# SchematicEagle.net
KiCad netlist of a schematic drawn in EAGLE
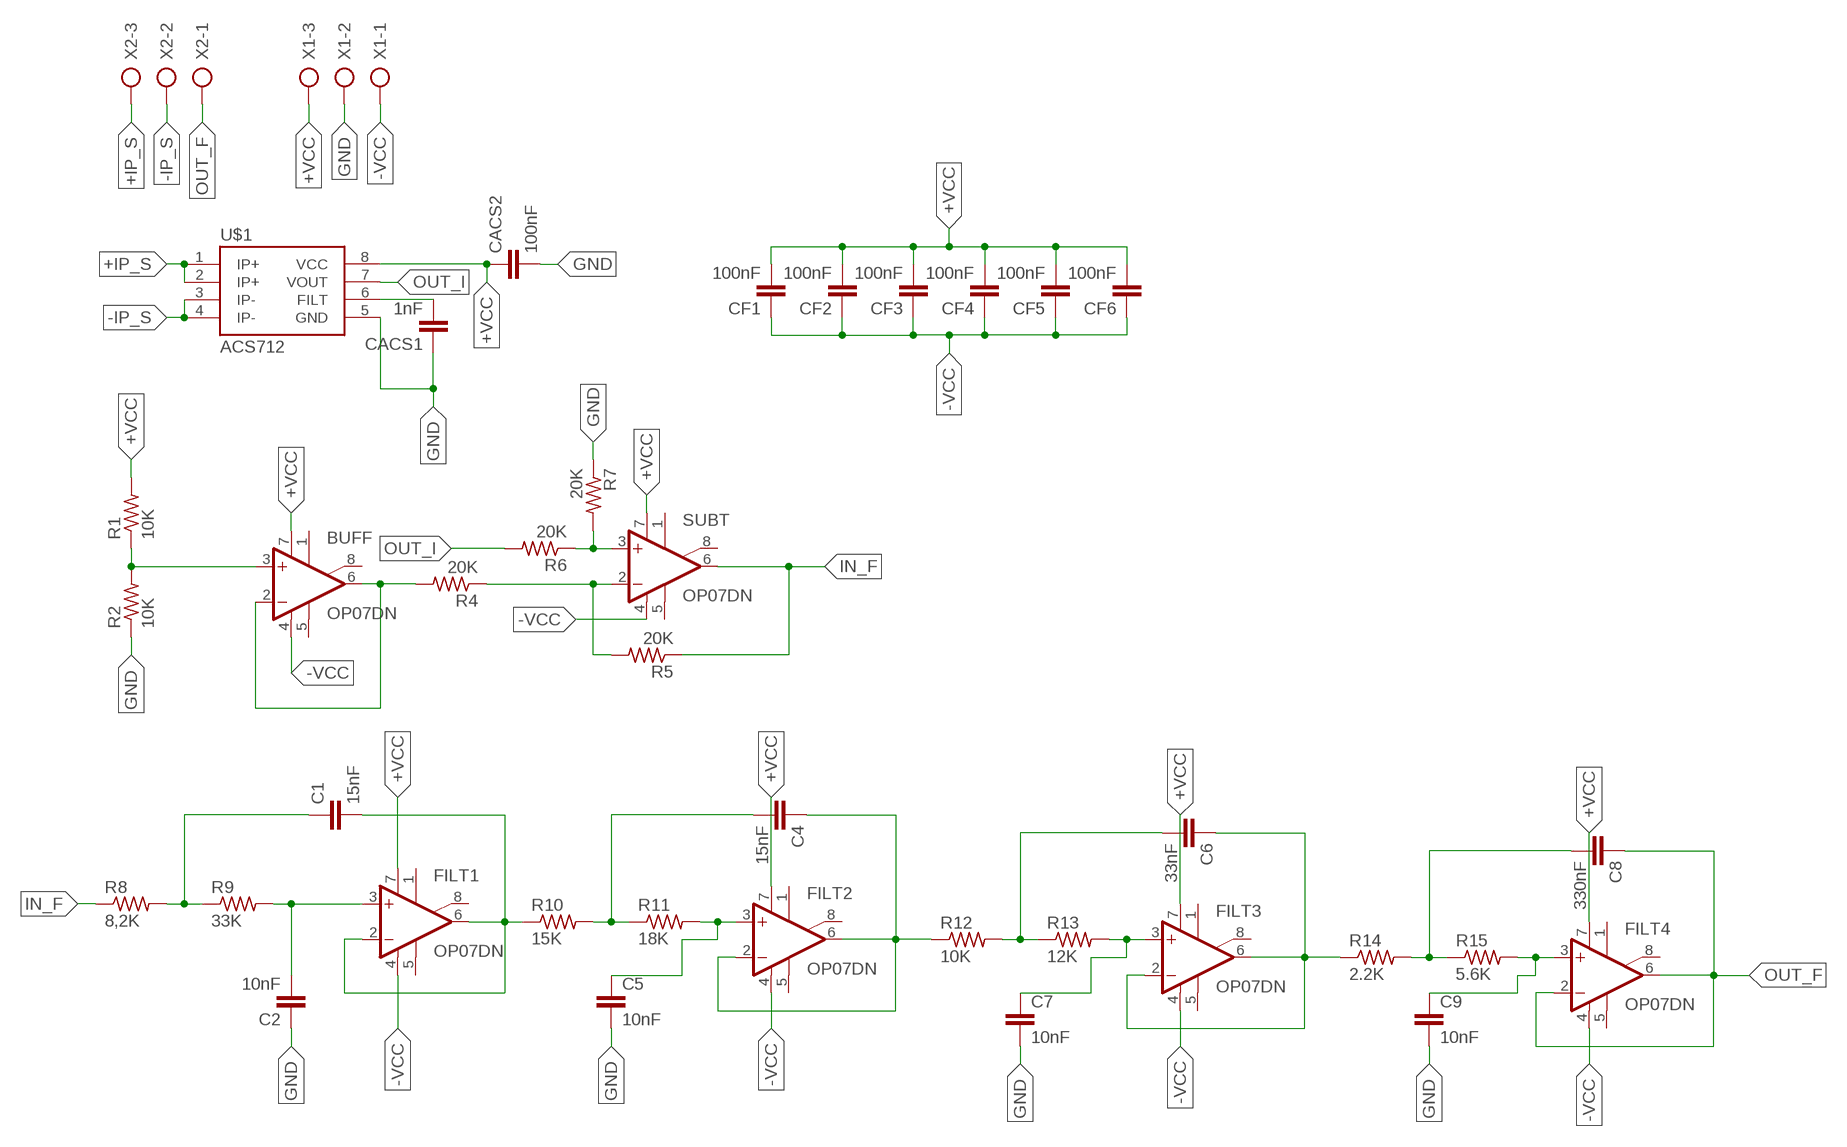
[diagram p0: schematic, sheet 1]

(export (version "E")
  (design (tool "Eeschema 10.0.6"))
  (components
    (comp (ref "BUFF")
      (value "OP07DN")
      (footprint "eagle-import:DIL08")
      (libsource (lib "eagle-import") (part "OP07ND"))
    )
    (comp (ref "C1")
      (value "15nF")
      (footprint "eagle-import:C050-024X044")
      (libsource (lib "eagle-import") (part "C-EU050-024X044"))
    )
    (comp (ref "C2")
      (value "10nF")
      (footprint "eagle-import:C050-024X044")
      (libsource (lib "eagle-import") (part "C-EU050-024X044"))
    )
    (comp (ref "C4")
      (value "15nF")
      (footprint "eagle-import:C050-024X044")
      (libsource (lib "eagle-import") (part "C-EU050-024X044"))
    )
    (comp (ref "C5")
      (value "10nF")
      (footprint "eagle-import:C050-024X044")
      (libsource (lib "eagle-import") (part "C-EU050-024X044"))
    )
    (comp (ref "C6")
      (value "33nF")
      (footprint "eagle-import:C050-024X044")
      (libsource (lib "eagle-import") (part "C-EU050-024X044"))
    )
    (comp (ref "C7")
      (value "10nF")
      (footprint "eagle-import:C050-024X044")
      (libsource (lib "eagle-import") (part "C-EU050-024X044"))
    )
    (comp (ref "C8")
      (value "330nF")
      (footprint "eagle-import:C050-024X044")
      (libsource (lib "eagle-import") (part "C-EU050-024X044"))
    )
    (comp (ref "C9")
      (value "10nF")
      (footprint "eagle-import:C050-024X044")
      (libsource (lib "eagle-import") (part "C-EU050-024X044"))
    )
    (comp (ref "CACS1")
      (value "1nF")
      (footprint "eagle-import:C050-024X044")
      (libsource (lib "eagle-import") (part "C-EU050-024X044"))
    )
    (comp (ref "CACS2")
      (value "100nF")
      (footprint "eagle-import:C050-024X044")
      (libsource (lib "eagle-import") (part "C-EU050-024X044"))
    )
    (comp (ref "CF1")
      (value "100nF")
      (footprint "eagle-import:C050-024X044")
      (libsource (lib "eagle-import") (part "C-EU050-024X044"))
    )
    (comp (ref "CF2")
      (value "100nF")
      (footprint "eagle-import:C050-024X044")
      (libsource (lib "eagle-import") (part "C-EU050-024X044"))
    )
    (comp (ref "CF3")
      (value "100nF")
      (footprint "eagle-import:C050-024X044")
      (libsource (lib "eagle-import") (part "C-EU050-024X044"))
    )
    (comp (ref "CF4")
      (value "100nF")
      (footprint "eagle-import:C050-024X044")
      (libsource (lib "eagle-import") (part "C-EU050-024X044"))
    )
    (comp (ref "CF5")
      (value "100nF")
      (footprint "eagle-import:C050-024X044")
      (libsource (lib "eagle-import") (part "C-EU050-024X044"))
    )
    (comp (ref "CF6")
      (value "100nF")
      (footprint "eagle-import:C050-024X044")
      (libsource (lib "eagle-import") (part "C-EU050-024X044"))
    )
    (comp (ref "FILT1")
      (value "OP07DN")
      (footprint "eagle-import:DIL08")
      (libsource (lib "eagle-import") (part "OP07ND"))
    )
    (comp (ref "FILT2")
      (value "OP07DN")
      (footprint "eagle-import:DIL08")
      (libsource (lib "eagle-import") (part "OP07ND"))
    )
    (comp (ref "FILT3")
      (value "OP07DN")
      (footprint "eagle-import:DIL08")
      (libsource (lib "eagle-import") (part "OP07ND"))
    )
    (comp (ref "FILT4")
      (value "OP07DN")
      (footprint "eagle-import:DIL08")
      (libsource (lib "eagle-import") (part "OP07ND"))
    )
    (comp (ref "R1")
      (value "10K")
      (footprint "eagle-import:0207_7")
      (libsource (lib "eagle-import") (part "R-US_0207/7"))
    )
    (comp (ref "R2")
      (value "10K")
      (footprint "eagle-import:0207_7")
      (libsource (lib "eagle-import") (part "R-US_0207/7"))
    )
    (comp (ref "R4")
      (value "20K")
      (footprint "eagle-import:0207_7")
      (libsource (lib "eagle-import") (part "R-US_0207/7"))
    )
    (comp (ref "R5")
      (value "20K")
      (footprint "eagle-import:0207_7")
      (libsource (lib "eagle-import") (part "R-US_0207/7"))
    )
    (comp (ref "R6")
      (value "20K")
      (footprint "eagle-import:0207_7")
      (libsource (lib "eagle-import") (part "R-US_0207/7"))
    )
    (comp (ref "R7")
      (value "20K")
      (footprint "eagle-import:0207_7")
      (libsource (lib "eagle-import") (part "R-US_0207/7"))
    )
    (comp (ref "R8")
      (value "8,2K")
      (footprint "eagle-import:0207_7")
      (libsource (lib "eagle-import") (part "R-US_0207/7"))
    )
    (comp (ref "R9")
      (value "33K")
      (footprint "eagle-import:0207_7")
      (libsource (lib "eagle-import") (part "R-US_0207/7"))
    )
    (comp (ref "R10")
      (value "15K")
      (footprint "eagle-import:0207_7")
      (libsource (lib "eagle-import") (part "R-US_0207/7"))
    )
    (comp (ref "R11")
      (value "18K")
      (footprint "eagle-import:0207_7")
      (libsource (lib "eagle-import") (part "R-US_0207/7"))
    )
    (comp (ref "R12")
      (value "10K")
      (footprint "eagle-import:0207_7")
      (libsource (lib "eagle-import") (part "R-US_0207/7"))
    )
    (comp (ref "R13")
      (value "12K")
      (footprint "eagle-import:0207_7")
      (libsource (lib "eagle-import") (part "R-US_0207/7"))
    )
    (comp (ref "R14")
      (value "2.2K")
      (footprint "eagle-import:0207_7")
      (libsource (lib "eagle-import") (part "R-US_0207/7"))
    )
    (comp (ref "R15")
      (value "5.6K")
      (footprint "eagle-import:0207_7")
      (libsource (lib "eagle-import") (part "R-US_0207/7"))
    )
    (comp (ref "SUBT")
      (value "OP07DN")
      (footprint "eagle-import:DIL08")
      (libsource (lib "eagle-import") (part "OP07ND"))
    )
    (comp (ref "U$1")
      (value "ACS712")
      (footprint "eagle-import:SO08")
      (libsource (lib "eagle-import") (part "ACS712"))
    )
    (comp (ref "X1")
      (value "AK500/3")
      (footprint "eagle-import:AK500_3")
      (libsource (lib "eagle-import") (part "AK500/3"))
    )
    (comp (ref "X2")
      (value "AK500/3")
      (footprint "eagle-import:AK500_3")
      (libsource (lib "eagle-import") (part "AK500/3"))
    )
  )
  (nets
    (net (code "1") (name "+IP_S") (class "Default")
      (node (ref "U$1") (pin "1") (pinfunction "IP+_1") (pintype "bidirectional"))
      (node (ref "U$1") (pin "2") (pinfunction "IP+_2") (pintype "bidirectional"))
      (node (ref "X2") (pin "3") (pinfunction "KL_3") (pintype "passive"))
    )
    (net (code "2") (name "+VCC") (class "Default")
      (node (ref "BUFF") (pin "7") (pinfunction "V+_7") (pintype "power_in"))
      (node (ref "CACS2") (pin "1") (pinfunction "1_1") (pintype "passive"))
      (node (ref "CF1") (pin "2") (pinfunction "2_2") (pintype "passive"))
      (node (ref "CF2") (pin "2") (pinfunction "2_2") (pintype "passive"))
      (node (ref "CF3") (pin "2") (pinfunction "2_2") (pintype "passive"))
      (node (ref "CF4") (pin "2") (pinfunction "2_2") (pintype "passive"))
      (node (ref "CF5") (pin "2") (pinfunction "2_2") (pintype "passive"))
      (node (ref "CF6") (pin "2") (pinfunction "2_2") (pintype "passive"))
      (node (ref "FILT1") (pin "7") (pinfunction "V+_7") (pintype "power_in"))
      (node (ref "FILT2") (pin "7") (pinfunction "V+_7") (pintype "power_in"))
      (node (ref "FILT3") (pin "7") (pinfunction "V+_7") (pintype "power_in"))
      (node (ref "FILT4") (pin "7") (pinfunction "V+_7") (pintype "power_in"))
      (node (ref "R1") (pin "2") (pinfunction "2_2") (pintype "passive"))
      (node (ref "SUBT") (pin "7") (pinfunction "V+_7") (pintype "power_in"))
      (node (ref "U$1") (pin "8") (pinfunction "VCC_8") (pintype "bidirectional"))
      (node (ref "X1") (pin "3") (pinfunction "KL_3") (pintype "passive"))
    )
    (net (code "3") (name "-IP_S") (class "Default")
      (node (ref "U$1") (pin "3") (pinfunction "IP-_3") (pintype "bidirectional"))
      (node (ref "U$1") (pin "4") (pinfunction "IP-_4") (pintype "bidirectional"))
      (node (ref "X2") (pin "2") (pinfunction "KL_2") (pintype "passive"))
    )
    (net (code "4") (name "-VCC") (class "Default")
      (node (ref "BUFF") (pin "4") (pinfunction "V-_4") (pintype "power_in"))
      (node (ref "CF1") (pin "1") (pinfunction "1_1") (pintype "passive"))
      (node (ref "CF2") (pin "1") (pinfunction "1_1") (pintype "passive"))
      (node (ref "CF3") (pin "1") (pinfunction "1_1") (pintype "passive"))
      (node (ref "CF4") (pin "1") (pinfunction "1_1") (pintype "passive"))
      (node (ref "CF5") (pin "1") (pinfunction "1_1") (pintype "passive"))
      (node (ref "CF6") (pin "1") (pinfunction "1_1") (pintype "passive"))
      (node (ref "FILT1") (pin "4") (pinfunction "V-_4") (pintype "power_in"))
      (node (ref "FILT2") (pin "4") (pinfunction "V-_4") (pintype "power_in"))
      (node (ref "FILT3") (pin "4") (pinfunction "V-_4") (pintype "power_in"))
      (node (ref "FILT4") (pin "4") (pinfunction "V-_4") (pintype "power_in"))
      (node (ref "SUBT") (pin "4") (pinfunction "V-_4") (pintype "power_in"))
      (node (ref "X1") (pin "1") (pinfunction "KL_1") (pintype "passive"))
    )
    (net (code "5") (name "GND") (class "Default")
      (node (ref "C2") (pin "1") (pinfunction "1_1") (pintype "passive"))
      (node (ref "C5") (pin "2") (pinfunction "2_2") (pintype "passive"))
      (node (ref "C7") (pin "2") (pinfunction "2_2") (pintype "passive"))
      (node (ref "C9") (pin "2") (pinfunction "2_2") (pintype "passive"))
      (node (ref "CACS1") (pin "1") (pinfunction "1_1") (pintype "passive"))
      (node (ref "CACS2") (pin "2") (pinfunction "2_2") (pintype "passive"))
      (node (ref "R2") (pin "1") (pinfunction "1_1") (pintype "passive"))
      (node (ref "R7") (pin "1") (pinfunction "1_1") (pintype "passive"))
      (node (ref "U$1") (pin "5") (pinfunction "GND_5") (pintype "bidirectional"))
      (node (ref "X1") (pin "2") (pinfunction "KL_2") (pintype "passive"))
    )
    (net (code "6") (name "IN_F") (class "Default")
      (node (ref "R5") (pin "1") (pinfunction "1_1") (pintype "passive"))
      (node (ref "R8") (pin "1") (pinfunction "1_1") (pintype "passive"))
      (node (ref "SUBT") (pin "6") (pinfunction "OUT_6") (pintype "output"))
    )
    (net (code "7") (name "Net-(BUFF-+IN)") (class "Default")
      (node (ref "BUFF") (pin "3") (pinfunction "+IN_3") (pintype "input"))
      (node (ref "R1") (pin "1") (pinfunction "1_1") (pintype "passive"))
      (node (ref "R2") (pin "2") (pinfunction "2_2") (pintype "passive"))
    )
    (net (code "8") (name "Net-(BUFF--IN)") (class "Default")
      (node (ref "BUFF") (pin "2") (pinfunction "-IN_2") (pintype "input"))
      (node (ref "BUFF") (pin "6") (pinfunction "OUT_6") (pintype "output"))
      (node (ref "R4") (pin "2") (pinfunction "2_2") (pintype "passive"))
    )
    (net (code "9") (name "Net-(C1-Pad1)") (class "Default")
      (node (ref "C1") (pin "1") (pinfunction "1_1") (pintype "passive"))
      (node (ref "R8") (pin "2") (pinfunction "2_2") (pintype "passive"))
      (node (ref "R9") (pin "1") (pinfunction "1_1") (pintype "passive"))
    )
    (net (code "10") (name "Net-(C4-Pad2)") (class "Default")
      (node (ref "C4") (pin "2") (pinfunction "2_2") (pintype "passive"))
      (node (ref "R10") (pin "2") (pinfunction "2_2") (pintype "passive"))
      (node (ref "R11") (pin "1") (pinfunction "1_1") (pintype "passive"))
    )
    (net (code "11") (name "Net-(C6-Pad2)") (class "Default")
      (node (ref "C6") (pin "2") (pinfunction "2_2") (pintype "passive"))
      (node (ref "R12") (pin "2") (pinfunction "2_2") (pintype "passive"))
      (node (ref "R13") (pin "1") (pinfunction "1_1") (pintype "passive"))
    )
    (net (code "12") (name "Net-(C8-Pad2)") (class "Default")
      (node (ref "C8") (pin "2") (pinfunction "2_2") (pintype "passive"))
      (node (ref "R14") (pin "2") (pinfunction "2_2") (pintype "passive"))
      (node (ref "R15") (pin "1") (pinfunction "1_1") (pintype "passive"))
    )
    (net (code "13") (name "Net-(FILT1-+IN)") (class "Default")
      (node (ref "C2") (pin "2") (pinfunction "2_2") (pintype "passive"))
      (node (ref "FILT1") (pin "3") (pinfunction "+IN_3") (pintype "input"))
      (node (ref "R9") (pin "2") (pinfunction "2_2") (pintype "passive"))
    )
    (net (code "14") (name "Net-(FILT1--IN)") (class "Default")
      (node (ref "C1") (pin "2") (pinfunction "2_2") (pintype "passive"))
      (node (ref "FILT1") (pin "2") (pinfunction "-IN_2") (pintype "input"))
      (node (ref "FILT1") (pin "6") (pinfunction "OUT_6") (pintype "output"))
      (node (ref "R10") (pin "1") (pinfunction "1_1") (pintype "passive"))
    )
    (net (code "15") (name "Net-(FILT2-+IN)") (class "Default")
      (node (ref "C5") (pin "1") (pinfunction "1_1") (pintype "passive"))
      (node (ref "FILT2") (pin "3") (pinfunction "+IN_3") (pintype "input"))
      (node (ref "R11") (pin "2") (pinfunction "2_2") (pintype "passive"))
    )
    (net (code "16") (name "Net-(FILT2--IN)") (class "Default")
      (node (ref "C4") (pin "1") (pinfunction "1_1") (pintype "passive"))
      (node (ref "FILT2") (pin "2") (pinfunction "-IN_2") (pintype "input"))
      (node (ref "FILT2") (pin "6") (pinfunction "OUT_6") (pintype "output"))
      (node (ref "R12") (pin "1") (pinfunction "1_1") (pintype "passive"))
    )
    (net (code "17") (name "Net-(FILT3-+IN)") (class "Default")
      (node (ref "C7") (pin "1") (pinfunction "1_1") (pintype "passive"))
      (node (ref "FILT3") (pin "3") (pinfunction "+IN_3") (pintype "input"))
      (node (ref "R13") (pin "2") (pinfunction "2_2") (pintype "passive"))
    )
    (net (code "18") (name "Net-(FILT3--IN)") (class "Default")
      (node (ref "C6") (pin "1") (pinfunction "1_1") (pintype "passive"))
      (node (ref "FILT3") (pin "2") (pinfunction "-IN_2") (pintype "input"))
      (node (ref "FILT3") (pin "6") (pinfunction "OUT_6") (pintype "output"))
      (node (ref "R14") (pin "1") (pinfunction "1_1") (pintype "passive"))
    )
    (net (code "19") (name "Net-(FILT4-+IN)") (class "Default")
      (node (ref "C9") (pin "1") (pinfunction "1_1") (pintype "passive"))
      (node (ref "FILT4") (pin "3") (pinfunction "+IN_3") (pintype "input"))
      (node (ref "R15") (pin "2") (pinfunction "2_2") (pintype "passive"))
    )
    (net (code "20") (name "Net-(SUBT-+IN)") (class "Default")
      (node (ref "R6") (pin "1") (pinfunction "1_1") (pintype "passive"))
      (node (ref "R7") (pin "2") (pinfunction "2_2") (pintype "passive"))
      (node (ref "SUBT") (pin "3") (pinfunction "+IN_3") (pintype "input"))
    )
    (net (code "21") (name "Net-(SUBT--IN)") (class "Default")
      (node (ref "R4") (pin "1") (pinfunction "1_1") (pintype "passive"))
      (node (ref "R5") (pin "2") (pinfunction "2_2") (pintype "passive"))
      (node (ref "SUBT") (pin "2") (pinfunction "-IN_2") (pintype "input"))
    )
    (net (code "22") (name "Net-(U$1-FILT)") (class "Default")
      (node (ref "CACS1") (pin "2") (pinfunction "2_2") (pintype "passive"))
      (node (ref "U$1") (pin "6") (pinfunction "FILT_6") (pintype "bidirectional"))
    )
    (net (code "23") (name "OUT_F") (class "Default")
      (node (ref "C8") (pin "1") (pinfunction "1_1") (pintype "passive"))
      (node (ref "FILT4") (pin "2") (pinfunction "-IN_2") (pintype "input"))
      (node (ref "FILT4") (pin "6") (pinfunction "OUT_6") (pintype "output"))
      (node (ref "X2") (pin "1") (pinfunction "KL_1") (pintype "passive"))
    )
    (net (code "24") (name "OUT_I") (class "Default")
      (node (ref "R6") (pin "2") (pinfunction "2_2") (pintype "passive"))
      (node (ref "U$1") (pin "7") (pinfunction "VOUT_7") (pintype "bidirectional"))
    )
    (net (code "25") (name "unconnected-(BUFF-ON1-Pad1)") (class "Default")
      (node (ref "BUFF") (pin "1") (pinfunction "ON1_1") (pintype "passive"))
    )
    (net (code "26") (name "unconnected-(BUFF-ON2-Pad8)") (class "Default")
      (node (ref "BUFF") (pin "8") (pinfunction "ON2_8") (pintype "passive"))
    )
    (net (code "27") (name "unconnected-(BUFF-OPT-Pad5)") (class "Default")
      (node (ref "BUFF") (pin "5") (pinfunction "OPT_5") (pintype "passive"))
    )
    (net (code "28") (name "unconnected-(FILT1-ON1-Pad1)") (class "Default")
      (node (ref "FILT1") (pin "1") (pinfunction "ON1_1") (pintype "passive"))
    )
    (net (code "29") (name "unconnected-(FILT1-ON2-Pad8)") (class "Default")
      (node (ref "FILT1") (pin "8") (pinfunction "ON2_8") (pintype "passive"))
    )
    (net (code "30") (name "unconnected-(FILT1-OPT-Pad5)") (class "Default")
      (node (ref "FILT1") (pin "5") (pinfunction "OPT_5") (pintype "passive"))
    )
    (net (code "31") (name "unconnected-(FILT2-ON1-Pad1)") (class "Default")
      (node (ref "FILT2") (pin "1") (pinfunction "ON1_1") (pintype "passive"))
    )
    (net (code "32") (name "unconnected-(FILT2-ON2-Pad8)") (class "Default")
      (node (ref "FILT2") (pin "8") (pinfunction "ON2_8") (pintype "passive"))
    )
    (net (code "33") (name "unconnected-(FILT2-OPT-Pad5)") (class "Default")
      (node (ref "FILT2") (pin "5") (pinfunction "OPT_5") (pintype "passive"))
    )
    (net (code "34") (name "unconnected-(FILT3-ON1-Pad1)") (class "Default")
      (node (ref "FILT3") (pin "1") (pinfunction "ON1_1") (pintype "passive"))
    )
    (net (code "35") (name "unconnected-(FILT3-ON2-Pad8)") (class "Default")
      (node (ref "FILT3") (pin "8") (pinfunction "ON2_8") (pintype "passive"))
    )
    (net (code "36") (name "unconnected-(FILT3-OPT-Pad5)") (class "Default")
      (node (ref "FILT3") (pin "5") (pinfunction "OPT_5") (pintype "passive"))
    )
    (net (code "37") (name "unconnected-(FILT4-ON1-Pad1)") (class "Default")
      (node (ref "FILT4") (pin "1") (pinfunction "ON1_1") (pintype "passive"))
    )
    (net (code "38") (name "unconnected-(FILT4-ON2-Pad8)") (class "Default")
      (node (ref "FILT4") (pin "8") (pinfunction "ON2_8") (pintype "passive"))
    )
    (net (code "39") (name "unconnected-(FILT4-OPT-Pad5)") (class "Default")
      (node (ref "FILT4") (pin "5") (pinfunction "OPT_5") (pintype "passive"))
    )
    (net (code "40") (name "unconnected-(SUBT-ON1-Pad1)") (class "Default")
      (node (ref "SUBT") (pin "1") (pinfunction "ON1_1") (pintype "passive"))
    )
    (net (code "41") (name "unconnected-(SUBT-ON2-Pad8)") (class "Default")
      (node (ref "SUBT") (pin "8") (pinfunction "ON2_8") (pintype "passive"))
    )
    (net (code "42") (name "unconnected-(SUBT-OPT-Pad5)") (class "Default")
      (node (ref "SUBT") (pin "5") (pinfunction "OPT_5") (pintype "passive"))
    )
  )
)
